# CPU.net
KiCad netlist of a schematic drawn in Altium Designer
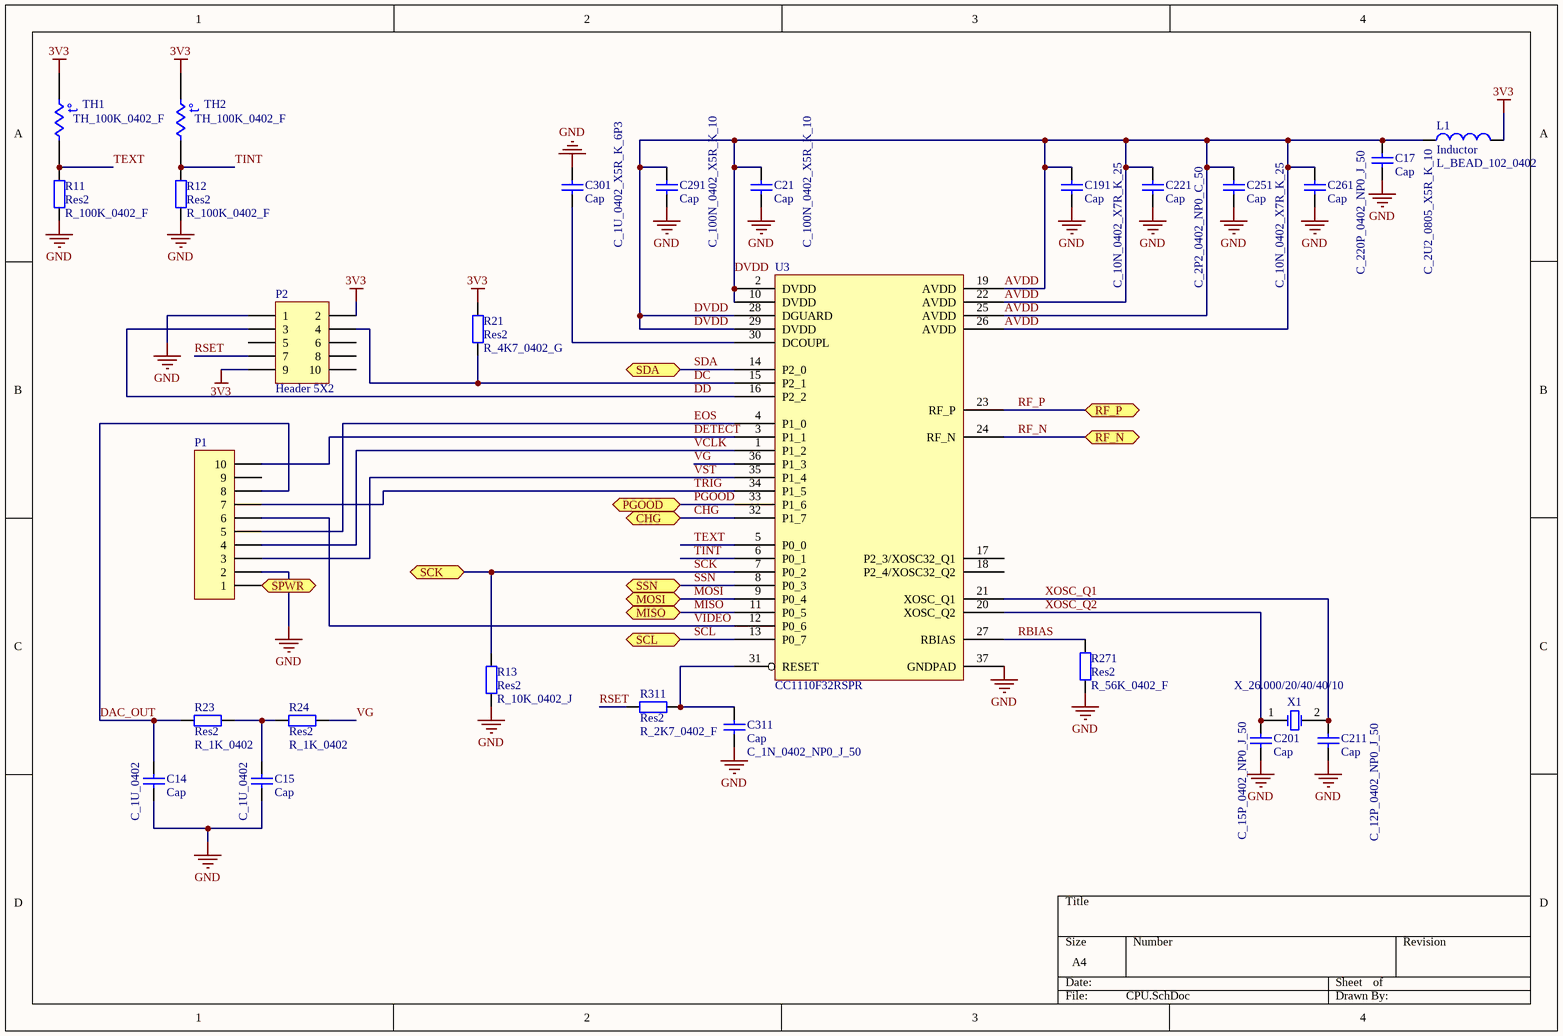
[diagram p0: CPU.SchDoc]

(export (version "E")
  (design (tool "Eeschema 10.0.6"))
  (components
    (comp (ref "C14")
      (value "Cap")
      (footprint "C_0402")
      (description "Capacitor")
      (fields (field (name "ALTIUM_VALUE") "C_1U_0402") (field (name "PUBLISHER") "Altium Limited"))
      (libsource (lib "Miscellaneous Devices") (part "Cap"))
    )
    (comp (ref "C15")
      (value "Cap")
      (footprint "C_0402")
      (description "Capacitor")
      (fields (field (name "ALTIUM_VALUE") "C_1U_0402") (field (name "PUBLISHER") "Altium Limited"))
      (libsource (lib "Miscellaneous Devices") (part "Cap"))
    )
    (comp (ref "C17")
      (value "Cap")
      (footprint "C_0805")
      (description "Capacitor")
      (fields (field (name "ALTIUM_VALUE") "C_2U2_0805_X5R_K_10") (field (name "PUBLISHER") "Altium Limited"))
      (libsource (lib "Miscellaneous Devices") (part "Cap"))
    )
    (comp (ref "C21")
      (value "Cap")
      (footprint "C_0402")
      (description "Capacitor")
      (fields
        (field (name "ALTIUM_VALUE") "C_100N_0402_X5R_K_10")
        (field (name "PUBLISHER") "Altium Limited")
      )
      (libsource (lib "Miscellaneous Devices") (part "Cap"))
    )
    (comp (ref "C191")
      (value "Cap")
      (footprint "C_0402")
      (description "Capacitor")
      (fields (field (name "ALTIUM_VALUE") "C_10N_0402_X7R_K_25") (field (name "PUBLISHER") "Altium Limited"))
      (libsource (lib "Miscellaneous Devices") (part "Cap"))
    )
    (comp (ref "C201")
      (value "Cap")
      (footprint "C_0402")
      (description "Capacitor")
      (fields (field (name "ALTIUM_VALUE") "C_15P_0402_NP0_J_50") (field (name "PUBLISHER") "Altium Limited"))
      (libsource (lib "Miscellaneous Devices") (part "Cap"))
    )
    (comp (ref "C211")
      (value "Cap")
      (footprint "C_0402")
      (description "Capacitor")
      (fields (field (name "ALTIUM_VALUE") "C_12P_0402_NP0_J_50") (field (name "PUBLISHER") "Altium Limited"))
      (libsource (lib "Miscellaneous Devices") (part "Cap"))
    )
    (comp (ref "C221")
      (value "Cap")
      (footprint "C_0402")
      (description "Capacitor")
      (fields (field (name "ALTIUM_VALUE") "C_2P2_0402_NP0_C_50") (field (name "PUBLISHER") "Altium Limited"))
      (libsource (lib "Miscellaneous Devices") (part "Cap"))
    )
    (comp (ref "C251")
      (value "Cap")
      (footprint "C_0402")
      (description "Capacitor")
      (fields (field (name "ALTIUM_VALUE") "C_10N_0402_X7R_K_25") (field (name "PUBLISHER") "Altium Limited"))
      (libsource (lib "Miscellaneous Devices") (part "Cap"))
    )
    (comp (ref "C261")
      (value "Cap")
      (footprint "C_0402")
      (description "Capacitor")
      (fields
        (field (name "ALTIUM_VALUE") "C_220P_0402_NP0_J_50")
        (field (name "PUBLISHER") "Altium Limited")
      )
      (libsource (lib "Miscellaneous Devices") (part "Cap"))
    )
    (comp (ref "C291")
      (value "Cap")
      (footprint "C_0402")
      (description "Capacitor")
      (fields
        (field (name "ALTIUM_VALUE") "C_100N_0402_X5R_K_10")
        (field (name "PUBLISHER") "Altium Limited")
      )
      (libsource (lib "Miscellaneous Devices") (part "Cap"))
    )
    (comp (ref "C301")
      (value "Cap")
      (footprint "C_0402")
      (description "Capacitor")
      (fields (field (name "ALTIUM_VALUE") "C_1U_0402_X5R_K_6P3") (field (name "PUBLISHER") "Altium Limited"))
      (libsource (lib "Miscellaneous Devices") (part "Cap"))
    )
    (comp (ref "C311")
      (value "Cap")
      (footprint "C_0402")
      (description "Capacitor")
      (fields (field (name "ALTIUM_VALUE") "C_1N_0402_NP0_J_50") (field (name "PUBLISHER") "Altium Limited"))
      (libsource (lib "Miscellaneous Devices") (part "Cap"))
    )
    (comp (ref "L1")
      (value "Inductor")
      (footprint "R_0402")
      (fields (field (name "ALTIUM_VALUE") "L_BEAD_102_0402") (field (name "PUBLISHER") "Altium Limited"))
      (libsource (lib "Miscellaneous Devices") (part "Inductor"))
    )
    (comp (ref "P1")
      (value "Header 10")
      (footprint "609-4377-ND Female")
      (description "Header, 10-Pin")
      (fields (field (name "PUBLISHER") "Altium Limited"))
      (libsource (lib "Miscellaneous Connectors") (part "Header 10"))
    )
    (comp (ref "P2")
      (value "Header 5X2")
      (footprint "SMD HEADER")
      (description "Header, 5-Pin, Dual row")
      (fields (field (name "PUBLISHER") "Altium Limited"))
      (libsource (lib "Miscellaneous Connectors") (part "Header 5X2"))
    )
    (comp (ref "R11")
      (value "Res2")
      (footprint "R_0402")
      (description "Resistor")
      (fields (field (name "ALTIUM_VALUE") "R_100K_0402_F") (field (name "PUBLISHER") "Altium Limited"))
      (libsource (lib "Miscellaneous Devices") (part "Res2"))
    )
    (comp (ref "R12")
      (value "Res2")
      (footprint "R_0402")
      (description "Resistor")
      (fields (field (name "ALTIUM_VALUE") "R_100K_0402_F") (field (name "PUBLISHER") "Altium Limited"))
      (libsource (lib "Miscellaneous Devices") (part "Res2"))
    )
    (comp (ref "R13")
      (value "Res2")
      (footprint "R_0402")
      (description "Resistor")
      (fields (field (name "ALTIUM_VALUE") "R_10K_0402_J") (field (name "PUBLISHER") "Altium Limited"))
      (libsource (lib "Miscellaneous Devices") (part "Res2"))
    )
    (comp (ref "R21")
      (value "Res2")
      (footprint "R_0402")
      (description "Resistor")
      (fields (field (name "ALTIUM_VALUE") "R_4K7_0402_G") (field (name "PUBLISHER") "Altium Limited"))
      (libsource (lib "Miscellaneous Devices") (part "Res2"))
    )
    (comp (ref "R23")
      (value "Res2")
      (footprint "R_0402")
      (description "Resistor")
      (fields (field (name "ALTIUM_VALUE") "R_1K_0402") (field (name "PUBLISHER") "Altium Limited"))
      (libsource (lib "") (part "Res2_1"))
    )
    (comp (ref "R24")
      (value "Res2")
      (footprint "R_0402")
      (description "Resistor")
      (fields (field (name "ALTIUM_VALUE") "R_1K_0402") (field (name "PUBLISHER") "Altium Limited"))
      (libsource (lib "") (part "Res2_1"))
    )
    (comp (ref "R271")
      (value "Res2")
      (footprint "R_0402")
      (description "Resistor")
      (fields (field (name "ALTIUM_VALUE") "R_56K_0402_F") (field (name "PUBLISHER") "Altium Limited"))
      (libsource (lib "Miscellaneous Devices") (part "Res2"))
    )
    (comp (ref "R311")
      (value "Res2")
      (footprint "R_0402")
      (description "Resistor")
      (fields (field (name "ALTIUM_VALUE") "R_2K7_0402_F") (field (name "PUBLISHER") "Altium Limited"))
      (libsource (lib "") (part "Res2_2"))
    )
    (comp (ref "TH1")
      (value "TH_100K_0402_F")
      (footprint "R_0402")
      (description "Thermistor")
      (fields (field (name "Comment") "Res Thermal") (field (name "PUBLISHER") "Altium Limited"))
      (libsource (lib "Miscellaneous Devices") (part "Res Thermal"))
    )
    (comp (ref "TH2")
      (value "TH_100K_0402_F")
      (footprint "R_0402")
      (description "Thermistor")
      (fields (field (name "Comment") "Res Thermal") (field (name "PUBLISHER") "Altium Limited"))
      (libsource (lib "Miscellaneous Devices") (part "Res Thermal"))
    )
    (comp (ref "U3")
      (value "CC1110F32RSPR")
      (footprint "TI_QFP36")
      (description "RF Microcontrollers (MCU) True System-on-Chip")
      (fields (field (name "MANUFACTURER") "Texas Instruments"))
      (libsource (lib "BrewBit") (part "CC1110F32RSPR"))
    )
    (comp (ref "X1")
      (value "X_26.000/20/40/40/10")
      (footprint "NX3225GA")
      (description "Crystal Oscillator")
      (fields (field (name "PUBLISHER") "Altium Limited"))
      (libsource (lib "Miscellaneous Devices") (part "XTAL"))
    )
  )
  (nets
    (net (code "1") (name "/AVDD") (class "Default")
      (node (ref "C17") (pin "2") (pinfunction "2_2") (pintype "passive"))
      (node (ref "C191") (pin "2") (pinfunction "2_2") (pintype "passive"))
      (node (ref "C21") (pin "2") (pinfunction "2_2") (pintype "passive"))
      (node (ref "C221") (pin "2") (pinfunction "2_2") (pintype "passive"))
      (node (ref "C251") (pin "2") (pinfunction "2_2") (pintype "passive"))
      (node (ref "C261") (pin "2") (pinfunction "2_2") (pintype "passive"))
      (node (ref "C291") (pin "2") (pinfunction "2_2") (pintype "passive"))
      (node (ref "L1") (pin "1") (pinfunction "1_1") (pintype "passive"))
      (node (ref "U3") (pin "10") (pinfunction "DVDD_10") (pintype "passive"))
      (node (ref "U3") (pin "19") (pinfunction "AVDD_19") (pintype "passive"))
      (node (ref "U3") (pin "2") (pinfunction "DVDD_2") (pintype "passive"))
      (node (ref "U3") (pin "22") (pinfunction "AVDD_22") (pintype "passive"))
      (node (ref "U3") (pin "25") (pinfunction "AVDD_25") (pintype "passive"))
      (node (ref "U3") (pin "26") (pinfunction "AVDD_26") (pintype "passive"))
      (node (ref "U3") (pin "28") (pinfunction "DGUARD_28") (pintype "passive"))
      (node (ref "U3") (pin "29") (pinfunction "DVDD_29") (pintype "passive"))
    )
    (net (code "2") (name "/CHG") (class "Default")
      (node (ref "U3") (pin "32") (pinfunction "P1_7_32") (pintype "passive"))
    )
    (net (code "3") (name "/DAC_OUT") (class "Default")
      (node (ref "C14") (pin "2") (pinfunction "2_2") (pintype "passive"))
      (node (ref "P1") (pin "8") (pinfunction "8_8") (pintype "passive"))
      (node (ref "R23") (pin "2") (pinfunction "2_2") (pintype "passive"))
    )
    (net (code "4") (name "/DC") (class "Default")
      (node (ref "P2") (pin "4") (pinfunction "4_4") (pintype "passive"))
      (node (ref "R21") (pin "1") (pinfunction "1_1") (pintype "passive"))
      (node (ref "U3") (pin "15") (pinfunction "P2_1_15") (pintype "passive"))
    )
    (net (code "5") (name "/DD") (class "Default")
      (node (ref "P2") (pin "3") (pinfunction "3_3") (pintype "passive"))
      (node (ref "U3") (pin "16") (pinfunction "P2_2_16") (pintype "passive"))
    )
    (net (code "6") (name "/DETECT") (class "Default")
      (node (ref "P1") (pin "10") (pinfunction "10_10") (pintype "passive"))
      (node (ref "U3") (pin "3") (pinfunction "P1_1_3") (pintype "passive"))
    )
    (net (code "7") (name "/EOS") (class "Default")
      (node (ref "P1") (pin "5") (pinfunction "5_5") (pintype "passive"))
      (node (ref "U3") (pin "4") (pinfunction "P1_0_4") (pintype "passive"))
    )
    (net (code "8") (name "/MISO") (class "Default")
      (node (ref "U3") (pin "11") (pinfunction "P0_5_11") (pintype "passive"))
    )
    (net (code "9") (name "/MOSI") (class "Default")
      (node (ref "U3") (pin "9") (pinfunction "P0_4_9") (pintype "passive"))
    )
    (net (code "10") (name "/PGOOD") (class "Default")
      (node (ref "U3") (pin "33") (pinfunction "P1_6_33") (pintype "passive"))
    )
    (net (code "11") (name "/RBIAS") (class "Default")
      (node (ref "R271") (pin "2") (pinfunction "2_2") (pintype "passive"))
      (node (ref "U3") (pin "27") (pinfunction "RBIAS_27") (pintype "passive"))
    )
    (net (code "12") (name "/RF_N") (class "Default")
      (node (ref "U3") (pin "24") (pinfunction "RF_N_24") (pintype "passive"))
    )
    (net (code "13") (name "/RF_P") (class "Default")
      (node (ref "U3") (pin "23") (pinfunction "RF_P_23") (pintype "passive"))
    )
    (net (code "14") (name "/RSET") (class "Default")
      (node (ref "P2") (pin "7") (pinfunction "7_7") (pintype "passive"))
      (node (ref "R311") (pin "1") (pinfunction "1_1") (pintype "passive"))
    )
    (net (code "15") (name "/SCK") (class "Default")
      (node (ref "R13") (pin "2") (pinfunction "2_2") (pintype "passive"))
      (node (ref "U3") (pin "7") (pinfunction "P0_2_7") (pintype "passive"))
    )
    (net (code "16") (name "/SCL") (class "Default")
      (node (ref "U3") (pin "13") (pinfunction "P0_7_13") (pintype "passive"))
    )
    (net (code "17") (name "/SDA") (class "Default")
      (node (ref "U3") (pin "14") (pinfunction "P2_0_14") (pintype "passive"))
    )
    (net (code "18") (name "/SPWR") (class "Default")
      (node (ref "P1") (pin "1") (pinfunction "1_1") (pintype "passive"))
    )
    (net (code "19") (name "/SSN") (class "Default")
      (node (ref "U3") (pin "8") (pinfunction "P0_3_8") (pintype "passive"))
    )
    (net (code "20") (name "/TEXT") (class "Default")
      (node (ref "R11") (pin "2") (pinfunction "2_2") (pintype "passive"))
      (node (ref "TH1") (pin "2") (pinfunction "2_2") (pintype "passive"))
      (node (ref "U3") (pin "5") (pinfunction "P0_0_5") (pintype "passive"))
    )
    (net (code "21") (name "/TINT") (class "Default")
      (node (ref "R12") (pin "2") (pinfunction "2_2") (pintype "passive"))
      (node (ref "TH2") (pin "2") (pinfunction "2_2") (pintype "passive"))
      (node (ref "U3") (pin "6") (pinfunction "P0_1_6") (pintype "passive"))
    )
    (net (code "22") (name "/TRIG") (class "Default")
      (node (ref "P1") (pin "7") (pinfunction "7_7") (pintype "passive"))
      (node (ref "U3") (pin "34") (pinfunction "P1_5_34") (pintype "passive"))
    )
    (net (code "23") (name "/VCLK") (class "Default")
      (node (ref "P1") (pin "4") (pinfunction "4_4") (pintype "passive"))
      (node (ref "U3") (pin "1") (pinfunction "P1_2_1") (pintype "passive"))
    )
    (net (code "24") (name "/VG") (class "Default")
      (node (ref "R24") (pin "1") (pinfunction "1_1") (pintype "passive"))
      (node (ref "U3") (pin "36") (pinfunction "P1_3_36") (pintype "passive"))
    )
    (net (code "25") (name "/VIDEO") (class "Default")
      (node (ref "P1") (pin "6") (pinfunction "6_6") (pintype "passive"))
      (node (ref "U3") (pin "12") (pinfunction "P0_6_12") (pintype "passive"))
    )
    (net (code "26") (name "/VST") (class "Default")
      (node (ref "P1") (pin "3") (pinfunction "3_3") (pintype "passive"))
      (node (ref "U3") (pin "35") (pinfunction "P1_4_35") (pintype "passive"))
    )
    (net (code "27") (name "/XOSC_Q1") (class "Default")
      (node (ref "C211") (pin "2") (pinfunction "2_2") (pintype "passive"))
      (node (ref "U3") (pin "21") (pinfunction "XOSC_Q1_21") (pintype "passive"))
      (node (ref "X1") (pin "2") (pinfunction "OSC2_2") (pintype "passive"))
    )
    (net (code "28") (name "/XOSC_Q2") (class "Default")
      (node (ref "C201") (pin "2") (pinfunction "2_2") (pintype "passive"))
      (node (ref "U3") (pin "20") (pinfunction "XOSC_Q2_20") (pintype "passive"))
      (node (ref "X1") (pin "1") (pinfunction "OSC1_1") (pintype "passive"))
    )
    (net (code "29") (name "3V3") (class "Default")
      (node (ref "L1") (pin "2") (pinfunction "2_2") (pintype "passive"))
      (node (ref "P2") (pin "2") (pinfunction "2_2") (pintype "passive"))
      (node (ref "P2") (pin "9") (pinfunction "9_9") (pintype "passive"))
      (node (ref "R21") (pin "2") (pinfunction "2_2") (pintype "passive"))
      (node (ref "TH1") (pin "1") (pinfunction "1_1") (pintype "passive"))
      (node (ref "TH2") (pin "1") (pinfunction "1_1") (pintype "passive"))
    )
    (net (code "30") (name "GND") (class "Default")
      (node (ref "C14") (pin "1") (pinfunction "1_1") (pintype "passive"))
      (node (ref "C15") (pin "1") (pinfunction "1_1") (pintype "passive"))
      (node (ref "C17") (pin "1") (pinfunction "1_1") (pintype "passive"))
      (node (ref "C191") (pin "1") (pinfunction "1_1") (pintype "passive"))
      (node (ref "C201") (pin "1") (pinfunction "1_1") (pintype "passive"))
      (node (ref "C21") (pin "1") (pinfunction "1_1") (pintype "passive"))
      (node (ref "C211") (pin "1") (pinfunction "1_1") (pintype "passive"))
      (node (ref "C221") (pin "1") (pinfunction "1_1") (pintype "passive"))
      (node (ref "C251") (pin "1") (pinfunction "1_1") (pintype "passive"))
      (node (ref "C261") (pin "1") (pinfunction "1_1") (pintype "passive"))
      (node (ref "C291") (pin "1") (pinfunction "1_1") (pintype "passive"))
      (node (ref "C301") (pin "2") (pinfunction "2_2") (pintype "passive"))
      (node (ref "C311") (pin "1") (pinfunction "1_1") (pintype "passive"))
      (node (ref "P1") (pin "2") (pinfunction "2_2") (pintype "passive"))
      (node (ref "P2") (pin "1") (pinfunction "1_1") (pintype "passive"))
      (node (ref "R11") (pin "1") (pinfunction "1_1") (pintype "passive"))
      (node (ref "R12") (pin "1") (pinfunction "1_1") (pintype "passive"))
      (node (ref "R13") (pin "1") (pinfunction "1_1") (pintype "passive"))
      (node (ref "R271") (pin "1") (pinfunction "1_1") (pintype "passive"))
      (node (ref "U3") (pin "37") (pinfunction "GNDPAD_37") (pintype "passive"))
    )
    (net (code "31") (name "Net-(C15-Pad2)") (class "Default")
      (node (ref "C15") (pin "2") (pinfunction "2_2") (pintype "passive"))
      (node (ref "R23") (pin "1") (pinfunction "1_1") (pintype "passive"))
      (node (ref "R24") (pin "2") (pinfunction "2_2") (pintype "passive"))
    )
    (net (code "32") (name "Net-(U3-DCOUPL)") (class "Default")
      (node (ref "C301") (pin "1") (pinfunction "1_1") (pintype "passive"))
      (node (ref "U3") (pin "30") (pinfunction "DCOUPL_30") (pintype "passive"))
    )
    (net (code "33") (name "Net-(U3-RESET)") (class "Default")
      (node (ref "C311") (pin "2") (pinfunction "2_2") (pintype "passive"))
      (node (ref "R311") (pin "2") (pinfunction "2_2") (pintype "passive"))
      (node (ref "U3") (pin "31") (pinfunction "RESET_31") (pintype "passive"))
    )
    (net (code "34") (name "unconnected-(P1-Pad9)") (class "Default")
      (node (ref "P1") (pin "9") (pinfunction "9_9") (pintype "passive"))
    )
    (net (code "35") (name "unconnected-(P2-Pad5)") (class "Default")
      (node (ref "P2") (pin "5") (pinfunction "5_5") (pintype "passive"))
    )
    (net (code "36") (name "unconnected-(P2-Pad6)") (class "Default")
      (node (ref "P2") (pin "6") (pinfunction "6_6") (pintype "passive"))
    )
    (net (code "37") (name "unconnected-(P2-Pad8)") (class "Default")
      (node (ref "P2") (pin "8") (pinfunction "8_8") (pintype "passive"))
    )
    (net (code "38") (name "unconnected-(P2-Pad10)") (class "Default")
      (node (ref "P2") (pin "10") (pinfunction "10_10") (pintype "passive"))
    )
    (net (code "39") (name "unconnected-(U3-P2_3{slash}XOSC32_Q1-Pad17)") (class "Default")
      (node (ref "U3") (pin "17") (pinfunction "P2_3/XOSC32_Q1_17") (pintype "passive"))
    )
    (net (code "40") (name "unconnected-(U3-P2_4{slash}XOSC32_Q2-Pad18)") (class "Default")
      (node (ref "U3") (pin "18") (pinfunction "P2_4/XOSC32_Q2_18") (pintype "passive"))
    )
  )
)
